# vcnl36687s-breakout.net
KiCad netlist of a schematic drawn in EAGLE
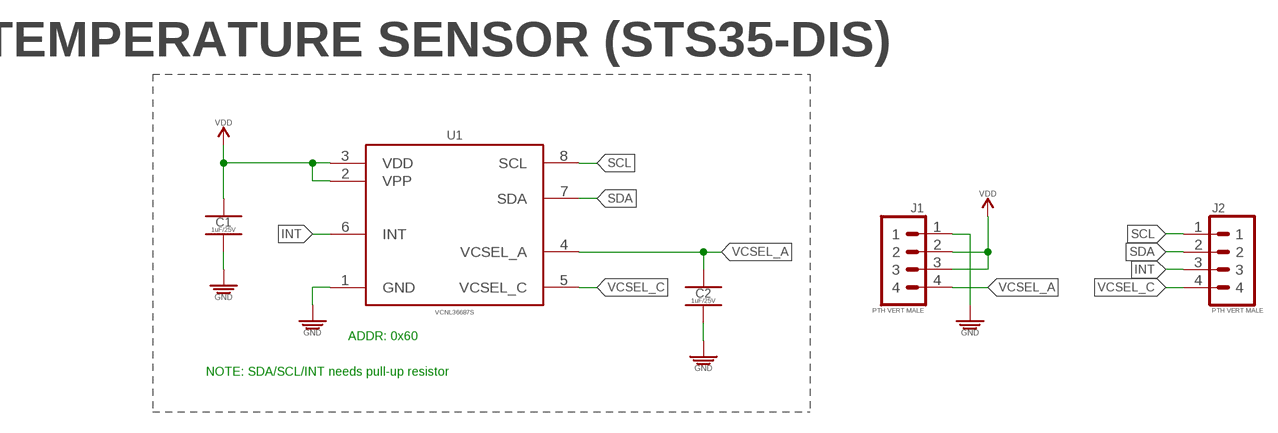
[diagram p0: schematic, sheet 1]

(export (version "E")
  (design (tool "Eeschema 10.0.6"))
  (components
    (comp (ref "C1")
      (value "1uF/25V")
      (footprint "eagle-import:CAPC1005X55_SMD-0402")
      (fields (field (name "MFR") "TDK Corporation") (field (name "MPN") "CGB2A1X5R1E105K033BC"))
      (libsource (lib "eagle-import") (part "1UF_CER_SMD-0402_25V-10%"))
    )
    (comp (ref "C2")
      (value "1uF/25V")
      (footprint "eagle-import:CAPC1005X55_SMD-0402")
      (fields (field (name "MFR") "TDK Corporation") (field (name "MPN") "CGB2A1X5R1E105K033BC"))
      (libsource (lib "eagle-import") (part "1UF_CER_SMD-0402_25V-10%"))
    )
    (comp (ref "J1")
      (value "PTH VERT MALE")
      (footprint "eagle-import:HDRV4W64P254_1X4_1016X254X838B")
      (fields (field (name "MFR") "Sullins Connector Solutions") (field (name "MPN") "PEC04SAAN"))
      (libsource (lib "eagle-import") (part "1X04_PTH_VERT_MALE_2.54MM"))
    )
    (comp (ref "J2")
      (value "PTH VERT MALE")
      (footprint "eagle-import:HDRV4W64P254_1X4_1016X254X838B")
      (fields (field (name "MFR") "Sullins Connector Solutions") (field (name "MPN") "PEC04SAAN"))
      (libsource (lib "eagle-import") (part "1X04_PTH_VERT_MALE_2.54MM"))
    )
    (comp (ref "U1")
      (value "VCNL36687S")
      (footprint "eagle-import:SON77P200X305X100-8N")
      (fields (field (name "MFR") "Vishay Semiconductor Opto Division"))
      (libsource (lib "eagle-import") (part "VCNL36687S"))
    )
  )
  (nets
    (net (code "1") (name "GND") (class "Default")
      (node (ref "C1") (pin "2") (pinfunction "2_2") (pintype "passive"))
      (node (ref "C2") (pin "2") (pinfunction "2_2") (pintype "passive"))
      (node (ref "J1") (pin "1") (pinfunction "1_1") (pintype "passive"))
      (node (ref "U1") (pin "1") (pinfunction "GND_1") (pintype "power_in"))
    )
    (net (code "2") (name "INT") (class "Default")
      (node (ref "J2") (pin "3") (pinfunction "3_3") (pintype "passive"))
      (node (ref "U1") (pin "6") (pinfunction "INT_6") (pintype "bidirectional"))
    )
    (net (code "3") (name "SCL") (class "Default")
      (node (ref "J2") (pin "1") (pinfunction "1_1") (pintype "passive"))
      (node (ref "U1") (pin "8") (pinfunction "SCL_8") (pintype "bidirectional"))
    )
    (net (code "4") (name "SDA") (class "Default")
      (node (ref "J2") (pin "2") (pinfunction "2_2") (pintype "passive"))
      (node (ref "U1") (pin "7") (pinfunction "SDA_7") (pintype "bidirectional"))
    )
    (net (code "5") (name "VCSEL_A") (class "Default")
      (node (ref "C2") (pin "1") (pinfunction "1_1") (pintype "passive"))
      (node (ref "J1") (pin "4") (pinfunction "4_4") (pintype "passive"))
      (node (ref "U1") (pin "4") (pinfunction "VCSEL_A_4") (pintype "bidirectional"))
    )
    (net (code "6") (name "VCSEL_C") (class "Default")
      (node (ref "J2") (pin "4") (pinfunction "4_4") (pintype "passive"))
      (node (ref "U1") (pin "5") (pinfunction "VCSEL_C_5") (pintype "bidirectional"))
    )
    (net (code "7") (name "VDD") (class "Default")
      (node (ref "C1") (pin "1") (pinfunction "1_1") (pintype "passive"))
      (node (ref "J1") (pin "2") (pinfunction "2_2") (pintype "passive"))
      (node (ref "J1") (pin "3") (pinfunction "3_3") (pintype "passive"))
      (node (ref "U1") (pin "2") (pinfunction "VPP_2") (pintype "power_in"))
      (node (ref "U1") (pin "3") (pinfunction "VDD_3") (pintype "power_in"))
    )
  )
)
